# RCJ_OnStage2024_FC_sensors.net
KiCad netlist of a schematic drawn in Altium Designer
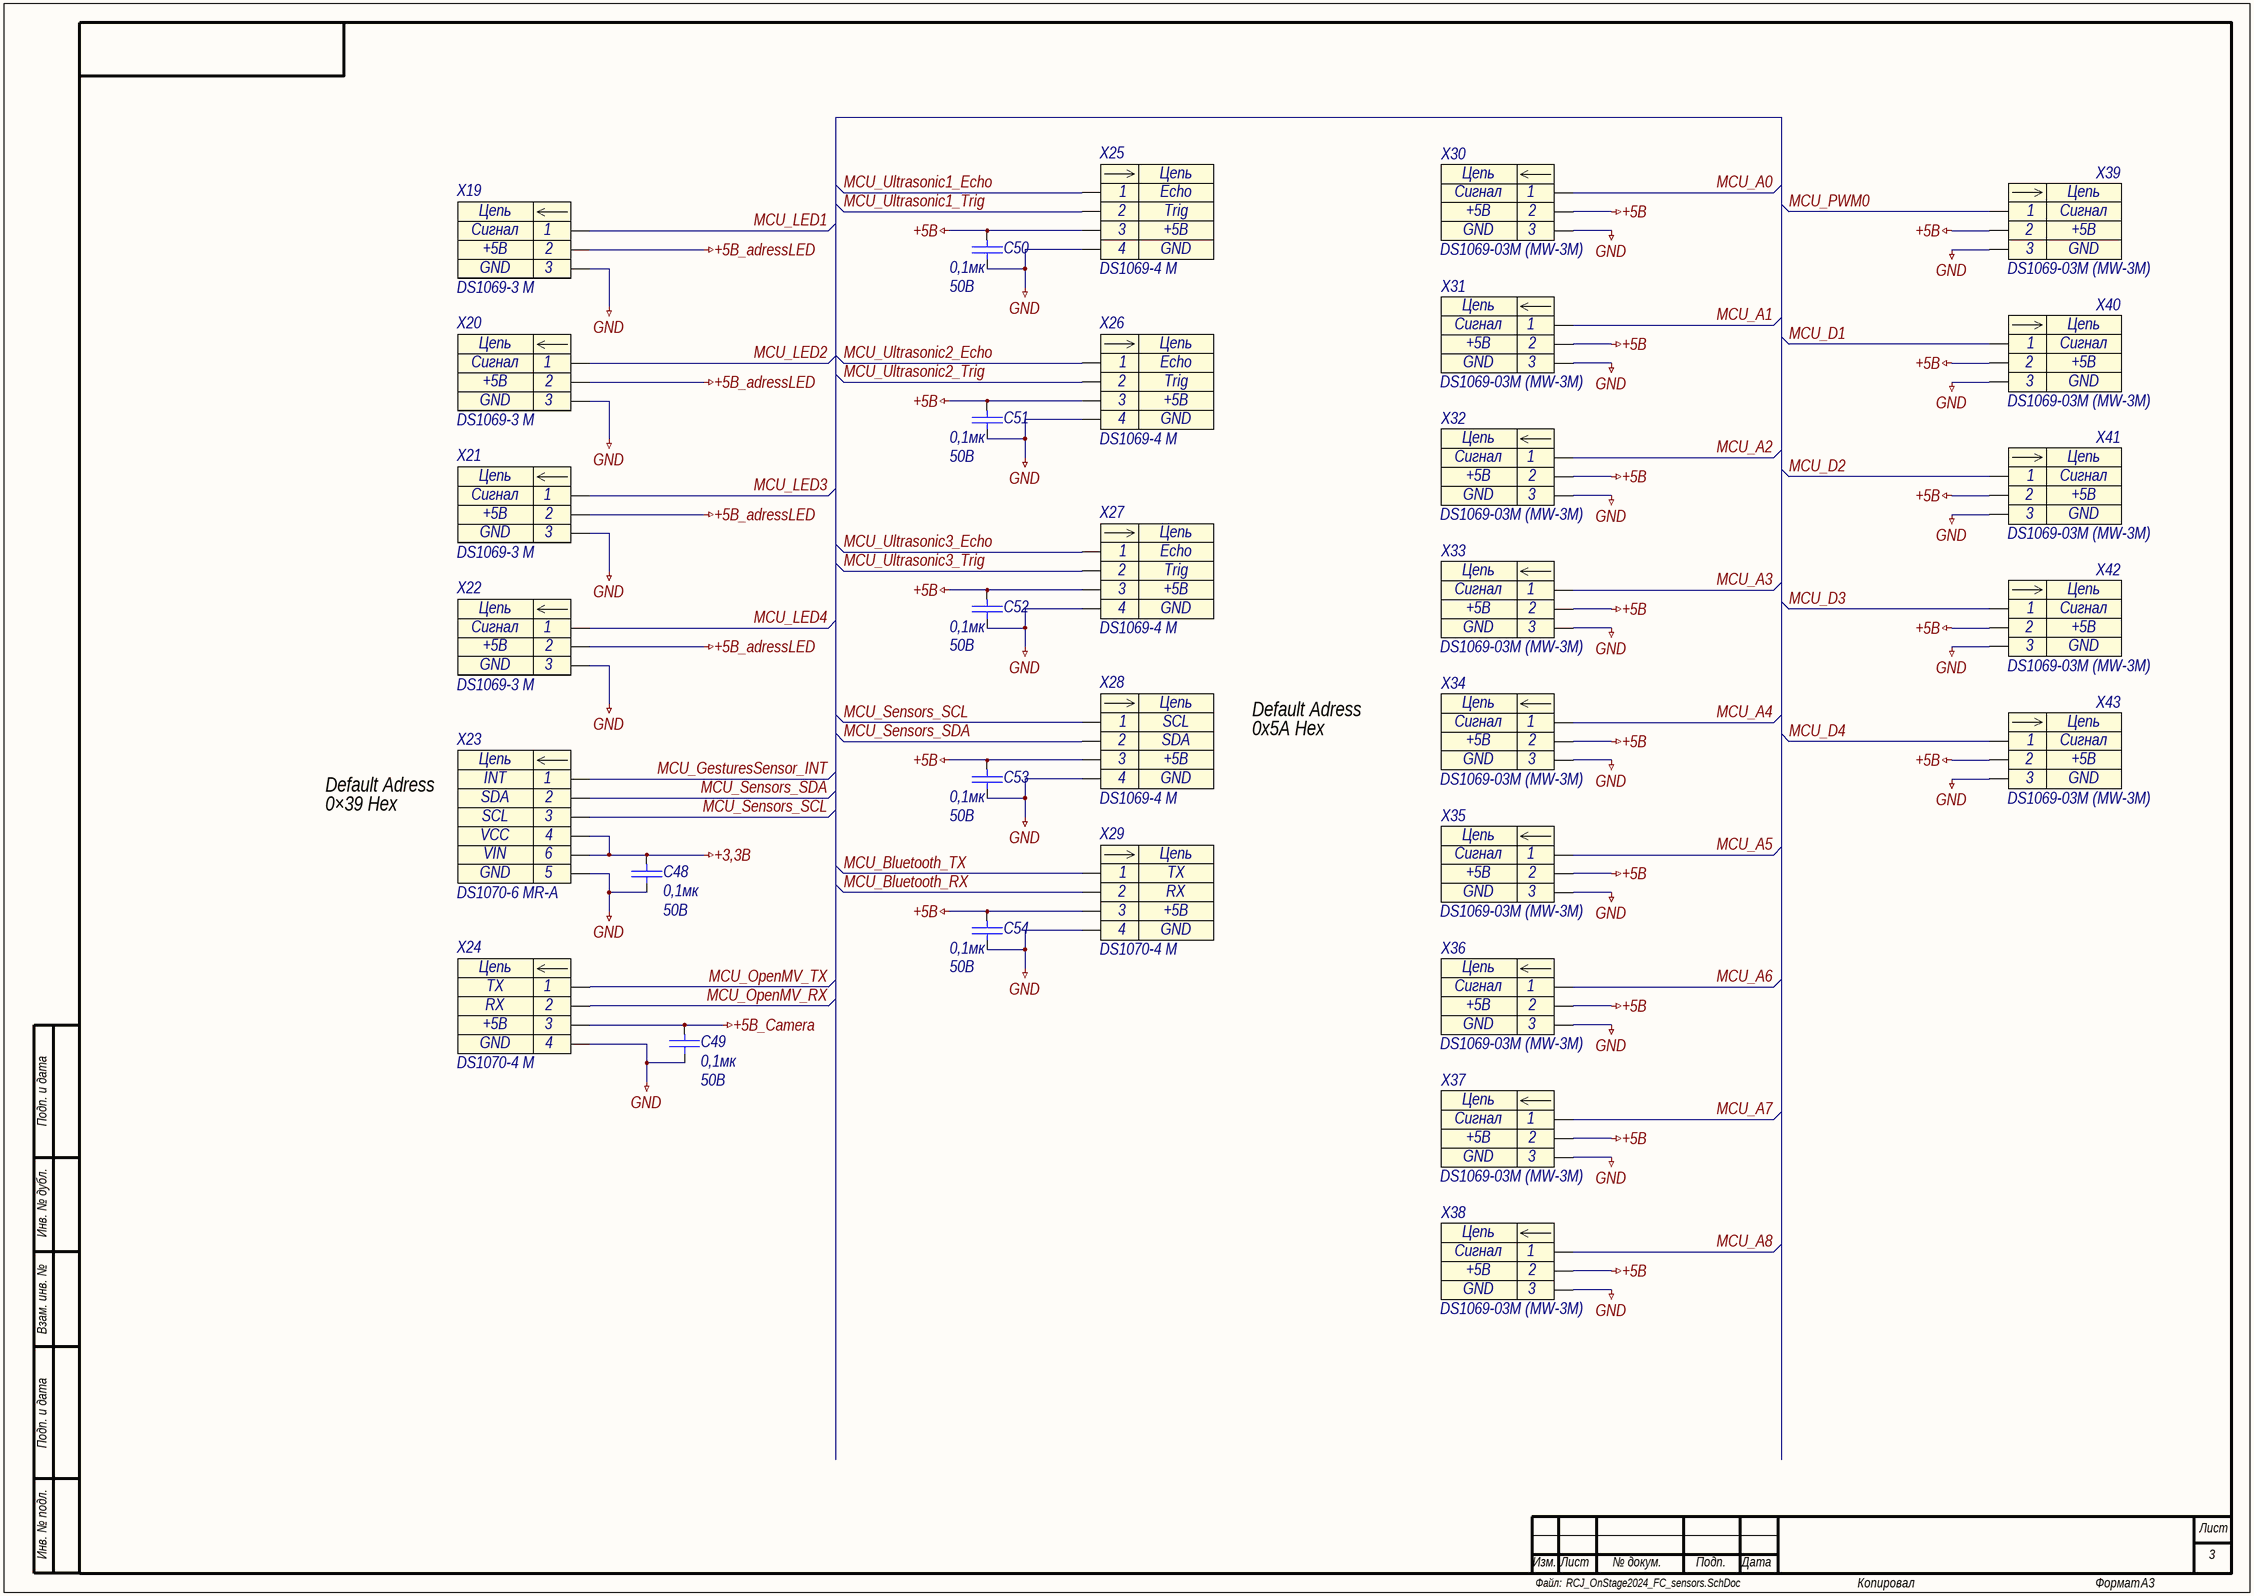
[diagram p0: RCJ_OnStage2024_FC_sensors.SchDoc]

(export (version "E")
  (design (tool "Eeschema 10.0.6"))
  (components
    (comp (ref "C48")
      (value "0,1мк")
      (footprint "C0603")
      (description "Конденсатор кер. 0,1мкФ 50В X7R")
      (fields (field (name "MANUFACTURER") "Murata") (field (name "VOLTAGE") "50В"))
      (libsource (lib "capacitors") (part "GRM188R71H104KA93D"))
    )
    (comp (ref "C49")
      (value "0,1мк")
      (footprint "C0603")
      (description "Конденсатор кер. 0,1мкФ 50В X7R")
      (fields (field (name "MANUFACTURER") "Murata") (field (name "VOLTAGE") "50В"))
      (libsource (lib "capacitors") (part "GRM188R71H104KA93D"))
    )
    (comp (ref "C50")
      (value "0,1мк")
      (footprint "C0603")
      (description "Конденсатор кер. 0,1мкФ 50В X7R")
      (fields (field (name "MANUFACTURER") "Murata") (field (name "VOLTAGE") "50В"))
      (libsource (lib "capacitors") (part "GRM188R71H104KA93D"))
    )
    (comp (ref "C51")
      (value "0,1мк")
      (footprint "C0603")
      (description "Конденсатор кер. 0,1мкФ 50В X7R")
      (fields (field (name "MANUFACTURER") "Murata") (field (name "VOLTAGE") "50В"))
      (libsource (lib "capacitors") (part "GRM188R71H104KA93D"))
    )
    (comp (ref "C52")
      (value "0,1мк")
      (footprint "C0603")
      (description "Конденсатор кер. 0,1мкФ 50В X7R")
      (fields (field (name "MANUFACTURER") "Murata") (field (name "VOLTAGE") "50В"))
      (libsource (lib "capacitors") (part "GRM188R71H104KA93D"))
    )
    (comp (ref "C53")
      (value "0,1мк")
      (footprint "C0603")
      (description "Конденсатор кер. 0,1мкФ 50В X7R")
      (fields (field (name "MANUFACTURER") "Murata") (field (name "VOLTAGE") "50В"))
      (libsource (lib "capacitors") (part "GRM188R71H104KA93D"))
    )
    (comp (ref "C54")
      (value "0,1мк")
      (footprint "C0603")
      (description "Конденсатор кер. 0,1мкФ 50В X7R")
      (fields (field (name "MANUFACTURER") "Murata") (field (name "VOLTAGE") "50В"))
      (libsource (lib "capacitors") (part "GRM188R71H104KA93D"))
    )
    (comp (ref "X19")
      (value "DS1069-3 M")
      (footprint "DS1070-3")
      (description "Вилка на плату 2.5мм открытая 3pin")
      (libsource (lib "connectors") (part "WF-3"))
    )
    (comp (ref "X20")
      (value "DS1069-3 M")
      (footprint "DS1070-3")
      (description "Вилка на плату 2.5мм открытая 3pin")
      (libsource (lib "connectors") (part "WF-3"))
    )
    (comp (ref "X21")
      (value "DS1069-3 M")
      (footprint "DS1070-3")
      (description "Вилка на плату 2.5мм открытая 3pin")
      (libsource (lib "connectors") (part "WF-3"))
    )
    (comp (ref "X22")
      (value "DS1069-3 M")
      (footprint "DS1070-3")
      (description "Вилка на плату 2.5мм открытая 3pin")
      (libsource (lib "connectors") (part "WF-3"))
    )
    (comp (ref "X23")
      (value "DS1070-6 MR-A")
      (footprint "DS1070-6")
      (description "Вилка на плату 2.54мм 6pin угловая закрытая тип А")
      (libsource (lib "connectors") (part "WF-6"))
    )
    (comp (ref "X24")
      (value "DS1070-4 M")
      (footprint "DS1070-4")
      (description "Вилка на плату 2.54мм открытая 4pin")
      (libsource (lib "") (part "WF-4_1"))
    )
    (comp (ref "X25")
      (value "DS1069-4 M")
      (footprint "DS1069-4")
      (description "Вилка на плату 2.5мм открытая 4pin")
      (libsource (lib "connectors") (part "WF-4"))
    )
    (comp (ref "X26")
      (value "DS1069-4 M")
      (footprint "DS1069-4")
      (description "Вилка на плату 2.5мм открытая 4pin")
      (libsource (lib "connectors") (part "WF-4"))
    )
    (comp (ref "X27")
      (value "DS1069-4 M")
      (footprint "DS1069-4")
      (description "Вилка на плату 2.5мм открытая 4pin")
      (libsource (lib "connectors") (part "WF-4"))
    )
    (comp (ref "X28")
      (value "DS1069-4 M")
      (footprint "DS1069-4")
      (description "Вилка на плату 2.5мм открытая 4pin")
      (libsource (lib "connectors") (part "WF-4"))
    )
    (comp (ref "X29")
      (value "DS1070-4 M")
      (footprint "DS1070-4")
      (description "Вилка на плату 2.54мм открытая 4pin")
      (libsource (lib "connectors") (part "WF-4"))
    )
    (comp (ref "X30")
      (value "DS1069-03M (MW-3M)")
      (footprint "PLS-3")
      (description "Разъем - 3 конт. прямая вилка на плату")
      (libsource (lib "") (part "PLS-3_1"))
    )
    (comp (ref "X31")
      (value "DS1069-03M (MW-3M)")
      (footprint "PLS-3")
      (description "Разъем - 3 конт. прямая вилка на плату")
      (libsource (lib "") (part "PLS-3_1"))
    )
    (comp (ref "X32")
      (value "DS1069-03M (MW-3M)")
      (footprint "PLS-3")
      (description "Разъем - 3 конт. прямая вилка на плату")
      (libsource (lib "") (part "PLS-3_1"))
    )
    (comp (ref "X33")
      (value "DS1069-03M (MW-3M)")
      (footprint "PLS-3")
      (description "Разъем - 3 конт. прямая вилка на плату")
      (libsource (lib "") (part "PLS-3_1"))
    )
    (comp (ref "X34")
      (value "DS1069-03M (MW-3M)")
      (footprint "PLS-3")
      (description "Разъем - 3 конт. прямая вилка на плату")
      (libsource (lib "") (part "PLS-3_1"))
    )
    (comp (ref "X35")
      (value "DS1069-03M (MW-3M)")
      (footprint "PLS-3")
      (description "Разъем - 3 конт. прямая вилка на плату")
      (libsource (lib "") (part "PLS-3_1"))
    )
    (comp (ref "X36")
      (value "DS1069-03M (MW-3M)")
      (footprint "PLS-3")
      (description "Разъем - 3 конт. прямая вилка на плату")
      (libsource (lib "") (part "PLS-3_1"))
    )
    (comp (ref "X37")
      (value "DS1069-03M (MW-3M)")
      (footprint "PLS-3")
      (description "Разъем - 3 конт. прямая вилка на плату")
      (libsource (lib "") (part "PLS-3_1"))
    )
    (comp (ref "X38")
      (value "DS1069-03M (MW-3M)")
      (footprint "PLS-3")
      (description "Разъем - 3 конт. прямая вилка на плату")
      (libsource (lib "") (part "PLS-3_1"))
    )
    (comp (ref "X39")
      (value "DS1069-03M (MW-3M)")
      (footprint "PLS-3")
      (description "Разъем - 3 конт. прямая вилка на плату")
      (libsource (lib "connectors") (part "PLS-3"))
    )
    (comp (ref "X40")
      (value "DS1069-03M (MW-3M)")
      (footprint "PLS-3")
      (description "Разъем - 3 конт. прямая вилка на плату")
      (libsource (lib "connectors") (part "PLS-3"))
    )
    (comp (ref "X41")
      (value "DS1069-03M (MW-3M)")
      (footprint "PLS-3")
      (description "Разъем - 3 конт. прямая вилка на плату")
      (libsource (lib "connectors") (part "PLS-3"))
    )
    (comp (ref "X42")
      (value "DS1069-03M (MW-3M)")
      (footprint "PLS-3")
      (description "Разъем - 3 конт. прямая вилка на плату")
      (libsource (lib "connectors") (part "PLS-3"))
    )
    (comp (ref "X43")
      (value "DS1069-03M (MW-3M)")
      (footprint "PLS-3")
      (description "Разъем - 3 конт. прямая вилка на плату")
      (libsource (lib "connectors") (part "PLS-3"))
    )
  )
  (nets
    (net (code "1") (name "+3,3В") (class "Default")
      (node (ref "C48") (pin "2") (pinfunction "2_2") (pintype "passive"))
      (node (ref "X23") (pin "4") (pinfunction "4_4") (pintype "passive"))
      (node (ref "X23") (pin "5") (pinfunction "5_5") (pintype "passive"))
    )
    (net (code "2") (name "+5В") (class "Default")
      (node (ref "C50") (pin "2") (pinfunction "2_2") (pintype "passive"))
      (node (ref "C51") (pin "2") (pinfunction "2_2") (pintype "passive"))
      (node (ref "C52") (pin "2") (pinfunction "2_2") (pintype "passive"))
      (node (ref "C53") (pin "2") (pinfunction "2_2") (pintype "passive"))
      (node (ref "C54") (pin "2") (pinfunction "2_2") (pintype "passive"))
      (node (ref "X25") (pin "3") (pinfunction "3_3") (pintype "passive"))
      (node (ref "X26") (pin "3") (pinfunction "3_3") (pintype "passive"))
      (node (ref "X27") (pin "3") (pinfunction "3_3") (pintype "passive"))
      (node (ref "X28") (pin "3") (pinfunction "3_3") (pintype "passive"))
      (node (ref "X29") (pin "3") (pinfunction "3_3") (pintype "passive"))
      (node (ref "X30") (pin "2") (pinfunction "2_2") (pintype "passive"))
      (node (ref "X31") (pin "2") (pinfunction "2_2") (pintype "passive"))
      (node (ref "X32") (pin "2") (pinfunction "2_2") (pintype "passive"))
      (node (ref "X33") (pin "2") (pinfunction "2_2") (pintype "passive"))
      (node (ref "X34") (pin "2") (pinfunction "2_2") (pintype "passive"))
      (node (ref "X35") (pin "2") (pinfunction "2_2") (pintype "passive"))
      (node (ref "X36") (pin "2") (pinfunction "2_2") (pintype "passive"))
      (node (ref "X37") (pin "2") (pinfunction "2_2") (pintype "passive"))
      (node (ref "X38") (pin "2") (pinfunction "2_2") (pintype "passive"))
      (node (ref "X39") (pin "2") (pinfunction "2_2") (pintype "passive"))
      (node (ref "X40") (pin "2") (pinfunction "2_2") (pintype "passive"))
      (node (ref "X41") (pin "2") (pinfunction "2_2") (pintype "passive"))
      (node (ref "X42") (pin "2") (pinfunction "2_2") (pintype "passive"))
      (node (ref "X43") (pin "2") (pinfunction "2_2") (pintype "passive"))
    )
    (net (code "3") (name "+5В_Camera") (class "Default")
      (node (ref "C49") (pin "2") (pinfunction "2_2") (pintype "passive"))
      (node (ref "X24") (pin "3") (pinfunction "3_3") (pintype "passive"))
    )
    (net (code "4") (name "+5В_adressLED") (class "Default")
      (node (ref "X19") (pin "2") (pinfunction "2_2") (pintype "passive"))
      (node (ref "X20") (pin "2") (pinfunction "2_2") (pintype "passive"))
      (node (ref "X21") (pin "2") (pinfunction "2_2") (pintype "passive"))
      (node (ref "X22") (pin "2") (pinfunction "2_2") (pintype "passive"))
    )
    (net (code "5") (name "/MCU_A0") (class "Default")
      (node (ref "X30") (pin "1") (pinfunction "1_1") (pintype "passive"))
    )
    (net (code "6") (name "/MCU_A1") (class "Default")
      (node (ref "X31") (pin "1") (pinfunction "1_1") (pintype "passive"))
    )
    (net (code "7") (name "/MCU_A2") (class "Default")
      (node (ref "X32") (pin "1") (pinfunction "1_1") (pintype "passive"))
    )
    (net (code "8") (name "/MCU_A3") (class "Default")
      (node (ref "X33") (pin "1") (pinfunction "1_1") (pintype "passive"))
    )
    (net (code "9") (name "/MCU_A4") (class "Default")
      (node (ref "X34") (pin "1") (pinfunction "1_1") (pintype "passive"))
    )
    (net (code "10") (name "/MCU_A5") (class "Default")
      (node (ref "X35") (pin "1") (pinfunction "1_1") (pintype "passive"))
    )
    (net (code "11") (name "/MCU_A6") (class "Default")
      (node (ref "X36") (pin "1") (pinfunction "1_1") (pintype "passive"))
    )
    (net (code "12") (name "/MCU_A7") (class "Default")
      (node (ref "X37") (pin "1") (pinfunction "1_1") (pintype "passive"))
    )
    (net (code "13") (name "/MCU_A8") (class "Default")
      (node (ref "X38") (pin "1") (pinfunction "1_1") (pintype "passive"))
    )
    (net (code "14") (name "/MCU_Bluetooth_RX") (class "Default")
      (node (ref "X29") (pin "2") (pinfunction "2_2") (pintype "passive"))
    )
    (net (code "15") (name "/MCU_Bluetooth_TX") (class "Default")
      (node (ref "X29") (pin "1") (pinfunction "1_1") (pintype "passive"))
    )
    (net (code "16") (name "/MCU_D1") (class "Default")
      (node (ref "X40") (pin "1") (pinfunction "1_1") (pintype "passive"))
    )
    (net (code "17") (name "/MCU_D2") (class "Default")
      (node (ref "X41") (pin "1") (pinfunction "1_1") (pintype "passive"))
    )
    (net (code "18") (name "/MCU_D3") (class "Default")
      (node (ref "X42") (pin "1") (pinfunction "1_1") (pintype "passive"))
    )
    (net (code "19") (name "/MCU_D4") (class "Default")
      (node (ref "X43") (pin "1") (pinfunction "1_1") (pintype "passive"))
    )
    (net (code "20") (name "/MCU_GesturesSensor_INT") (class "Default")
      (node (ref "X23") (pin "1") (pinfunction "1_1") (pintype "passive"))
    )
    (net (code "21") (name "/MCU_LED1") (class "Default")
      (node (ref "X19") (pin "1") (pinfunction "1_1") (pintype "passive"))
    )
    (net (code "22") (name "/MCU_LED2") (class "Default")
      (node (ref "X20") (pin "1") (pinfunction "1_1") (pintype "passive"))
    )
    (net (code "23") (name "/MCU_LED3") (class "Default")
      (node (ref "X21") (pin "1") (pinfunction "1_1") (pintype "passive"))
    )
    (net (code "24") (name "/MCU_LED4") (class "Default")
      (node (ref "X22") (pin "1") (pinfunction "1_1") (pintype "passive"))
    )
    (net (code "25") (name "/MCU_OpenMV_RX") (class "Default")
      (node (ref "X24") (pin "2") (pinfunction "2_2") (pintype "passive"))
    )
    (net (code "26") (name "/MCU_OpenMV_TX") (class "Default")
      (node (ref "X24") (pin "1") (pinfunction "1_1") (pintype "passive"))
    )
    (net (code "27") (name "/MCU_PWM0") (class "Default")
      (node (ref "X39") (pin "1") (pinfunction "1_1") (pintype "passive"))
    )
    (net (code "28") (name "/MCU_Sensors_SCL") (class "Default")
      (node (ref "X23") (pin "3") (pinfunction "3_3") (pintype "passive"))
      (node (ref "X28") (pin "1") (pinfunction "1_1") (pintype "passive"))
    )
    (net (code "29") (name "/MCU_Sensors_SDA") (class "Default")
      (node (ref "X23") (pin "2") (pinfunction "2_2") (pintype "passive"))
      (node (ref "X28") (pin "2") (pinfunction "2_2") (pintype "passive"))
    )
    (net (code "30") (name "/MCU_Ultrasonic1_Echo") (class "Default")
      (node (ref "X25") (pin "1") (pinfunction "1_1") (pintype "passive"))
    )
    (net (code "31") (name "/MCU_Ultrasonic1_Trig") (class "Default")
      (node (ref "X25") (pin "2") (pinfunction "2_2") (pintype "passive"))
    )
    (net (code "32") (name "/MCU_Ultrasonic2_Echo") (class "Default")
      (node (ref "X26") (pin "1") (pinfunction "1_1") (pintype "passive"))
    )
    (net (code "33") (name "/MCU_Ultrasonic2_Trig") (class "Default")
      (node (ref "X26") (pin "2") (pinfunction "2_2") (pintype "passive"))
    )
    (net (code "34") (name "/MCU_Ultrasonic3_Echo") (class "Default")
      (node (ref "X27") (pin "1") (pinfunction "1_1") (pintype "passive"))
    )
    (net (code "35") (name "/MCU_Ultrasonic3_Trig") (class "Default")
      (node (ref "X27") (pin "2") (pinfunction "2_2") (pintype "passive"))
    )
    (net (code "36") (name "GND") (class "Default")
      (node (ref "C48") (pin "1") (pinfunction "1_1") (pintype "passive"))
      (node (ref "C49") (pin "1") (pinfunction "1_1") (pintype "passive"))
      (node (ref "C50") (pin "1") (pinfunction "1_1") (pintype "passive"))
      (node (ref "C51") (pin "1") (pinfunction "1_1") (pintype "passive"))
      (node (ref "C52") (pin "1") (pinfunction "1_1") (pintype "passive"))
      (node (ref "C53") (pin "1") (pinfunction "1_1") (pintype "passive"))
      (node (ref "C54") (pin "1") (pinfunction "1_1") (pintype "passive"))
      (node (ref "X19") (pin "3") (pinfunction "3_3") (pintype "passive"))
      (node (ref "X20") (pin "3") (pinfunction "3_3") (pintype "passive"))
      (node (ref "X21") (pin "3") (pinfunction "3_3") (pintype "passive"))
      (node (ref "X22") (pin "3") (pinfunction "3_3") (pintype "passive"))
      (node (ref "X23") (pin "6") (pinfunction "6_6") (pintype "passive"))
      (node (ref "X24") (pin "4") (pinfunction "4_4") (pintype "passive"))
      (node (ref "X25") (pin "4") (pinfunction "4_4") (pintype "passive"))
      (node (ref "X26") (pin "4") (pinfunction "4_4") (pintype "passive"))
      (node (ref "X27") (pin "4") (pinfunction "4_4") (pintype "passive"))
      (node (ref "X28") (pin "4") (pinfunction "4_4") (pintype "passive"))
      (node (ref "X29") (pin "4") (pinfunction "4_4") (pintype "passive"))
      (node (ref "X30") (pin "3") (pinfunction "3_3") (pintype "passive"))
      (node (ref "X31") (pin "3") (pinfunction "3_3") (pintype "passive"))
      (node (ref "X32") (pin "3") (pinfunction "3_3") (pintype "passive"))
      (node (ref "X33") (pin "3") (pinfunction "3_3") (pintype "passive"))
      (node (ref "X34") (pin "3") (pinfunction "3_3") (pintype "passive"))
      (node (ref "X35") (pin "3") (pinfunction "3_3") (pintype "passive"))
      (node (ref "X36") (pin "3") (pinfunction "3_3") (pintype "passive"))
      (node (ref "X37") (pin "3") (pinfunction "3_3") (pintype "passive"))
      (node (ref "X38") (pin "3") (pinfunction "3_3") (pintype "passive"))
      (node (ref "X39") (pin "3") (pinfunction "3_3") (pintype "passive"))
      (node (ref "X40") (pin "3") (pinfunction "3_3") (pintype "passive"))
      (node (ref "X41") (pin "3") (pinfunction "3_3") (pintype "passive"))
      (node (ref "X42") (pin "3") (pinfunction "3_3") (pintype "passive"))
      (node (ref "X43") (pin "3") (pinfunction "3_3") (pintype "passive"))
    )
  )
)
